# DVT-Discrete.net
KiCad netlist of a schematic drawn in Altium Designer
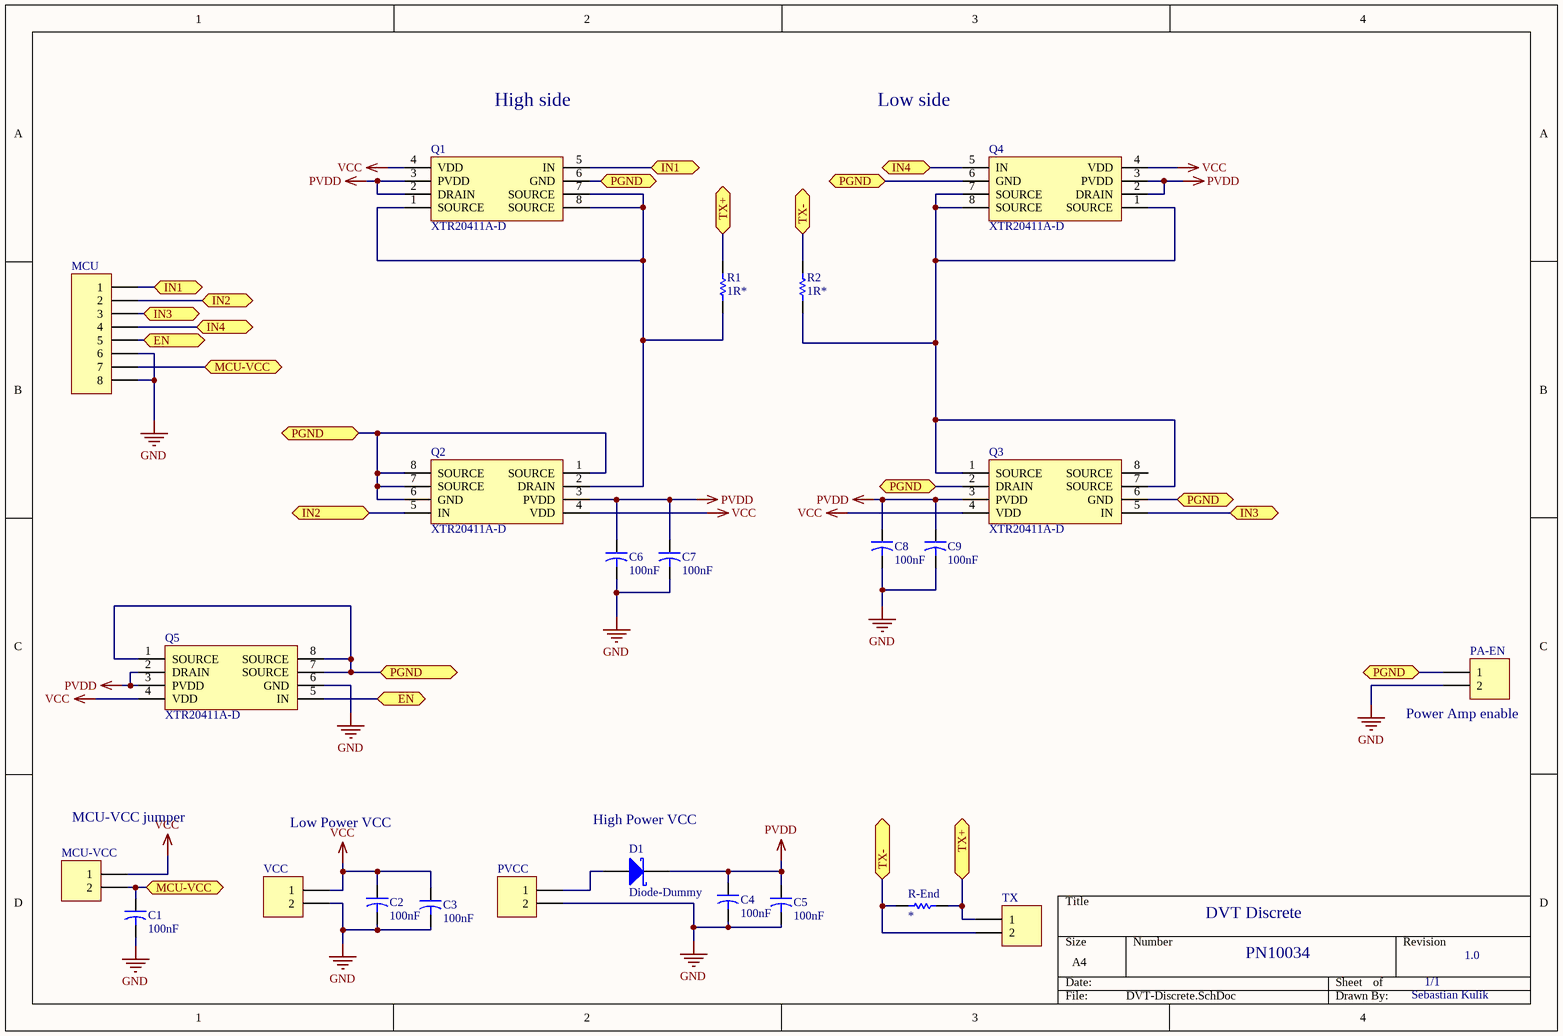
[diagram p0: DVT-Discrete.SchDoc]

(export (version "E")
  (design (tool "Eeschema 10.0.6"))
  (components
    (comp (ref "C1")
      (value "100nF")
      (footprint "Dummy-10mm")
      (description "Capacitor-Dummy-THT")
      (fields (field (name "PUBLISHER") "Sebastian Kulik"))
      (libsource (lib "Capacitors") (part "Capacitor-Dummy-THT"))
    )
    (comp (ref "C2")
      (value "100nF")
      (footprint "Dummy-10mm")
      (description "Capacitor-Dummy-THT")
      (fields (field (name "PUBLISHER") "Sebastian Kulik"))
      (libsource (lib "Capacitors") (part "Capacitor-Dummy-THT"))
    )
    (comp (ref "C3")
      (value "100nF")
      (footprint "Dummy-10mm")
      (description "Capacitor-Dummy-THT")
      (fields (field (name "PUBLISHER") "Sebastian Kulik"))
      (libsource (lib "Capacitors") (part "Capacitor-Dummy-THT"))
    )
    (comp (ref "C4")
      (value "100nF")
      (footprint "Dummy-10mm")
      (description "Capacitor-Dummy-THT")
      (fields (field (name "PUBLISHER") "Sebastian Kulik"))
      (libsource (lib "Capacitors") (part "Capacitor-Dummy-THT"))
    )
    (comp (ref "C5")
      (value "100nF")
      (footprint "Dummy-10mm")
      (description "Capacitor-Dummy-THT")
      (fields (field (name "PUBLISHER") "Sebastian Kulik"))
      (libsource (lib "Capacitors") (part "Capacitor-Dummy-THT"))
    )
    (comp (ref "C6")
      (value "100nF")
      (footprint "Dummy-10mm")
      (description "Capacitor-Dummy-THT")
      (fields (field (name "PUBLISHER") "Sebastian Kulik"))
      (libsource (lib "Capacitors") (part "Capacitor-Dummy-THT"))
    )
    (comp (ref "C7")
      (value "100nF")
      (footprint "Dummy-10mm")
      (description "Capacitor-Dummy-THT")
      (fields (field (name "PUBLISHER") "Sebastian Kulik"))
      (libsource (lib "Capacitors") (part "Capacitor-Dummy-THT"))
    )
    (comp (ref "C8")
      (value "100nF")
      (footprint "Dummy-10mm")
      (description "Capacitor-Dummy-THT")
      (fields (field (name "PUBLISHER") "Sebastian Kulik"))
      (libsource (lib "Capacitors") (part "Capacitor-Dummy-THT"))
    )
    (comp (ref "C9")
      (value "100nF")
      (footprint "Dummy-10mm")
      (description "Capacitor-Dummy-THT")
      (fields (field (name "PUBLISHER") "Sebastian Kulik"))
      (libsource (lib "Capacitors") (part "Capacitor-Dummy-THT"))
    )
    (comp (ref "D1")
      (value "Diode-Dummy")
      (footprint "DO-15-Dummy")
      (fields (field (name "PUBLISHER") "Sebastian Kulik"))
      (libsource (lib "Discrete") (part "Diode-Dummy"))
    )
    (comp (ref "MCU")
      (value "Plug_08_2.54")
      (footprint "HDR1X8_2.54")
      (description "Plug, 08-Pin")
      (fields (field (name "MANUFACTURER") "WE") (field (name "PUBLISHER") "Sebastian Kulik"))
      (libsource (lib "Connectors") (part "Plug_08_2.54"))
    )
    (comp (ref "MCU-VCC")
      (value "Plug_2_90_2.54")
      (footprint "HDR1X2")
      (description "Plug, 2-Pin")
      (fields (field (name "MANUFACTURER") "WE") (field (name "PUBLISHER") "Sebastian Kulik"))
      (libsource (lib "Connectors") (part "Plug_2_90_2.54"))
    )
    (comp (ref "PA-EN")
      (value "Plug_2_90_2.54")
      (footprint "HDR1X2")
      (description "Plug, 2-Pin")
      (fields (field (name "MANUFACTURER") "WE") (field (name "PUBLISHER") "Sebastian Kulik"))
      (libsource (lib "") (part "Plug_2_90_2.54_1"))
    )
    (comp (ref "PVCC")
      (value "PHOENIX_1715721")
      (footprint "Phoenix-2-5_08")
      (description "Phoenix, 2 pol, 5.08mm, 22A, 715721")
      (fields (field (name "MANUFACTURER") "Phoenix") (field (name "PUBLISHER") "Sebastian Kulik"))
      (libsource (lib "") (part "2Pol_1715721_1"))
    )
    (comp (ref "Q1")
      (value "XTR20411A-D")
      (footprint "DIP-8-Ceramic-HT")
      (description "Gate driver")
      (fields (field (name "MANUFACTURER") "X-Rel") (field (name "PUBLISHER") "Sebastian Kulik"))
      (libsource (lib "ICs") (part "XTR20411A-D"))
    )
    (comp (ref "Q2")
      (value "XTR20411A-D")
      (footprint "DIP-8-Ceramic-HT")
      (description "Gate driver")
      (fields (field (name "MANUFACTURER") "X-Rel") (field (name "PUBLISHER") "Sebastian Kulik"))
      (libsource (lib "") (part "XTR20411A-D_2"))
    )
    (comp (ref "Q3")
      (value "XTR20411A-D")
      (footprint "DIP-8-Ceramic-HT")
      (description "Gate driver")
      (fields (field (name "MANUFACTURER") "X-Rel") (field (name "PUBLISHER") "Sebastian Kulik"))
      (libsource (lib "") (part "XTR20411A-D_1"))
    )
    (comp (ref "Q4")
      (value "XTR20411A-D")
      (footprint "DIP-8-Ceramic-HT")
      (description "Gate driver")
      (fields (field (name "MANUFACTURER") "X-Rel") (field (name "PUBLISHER") "Sebastian Kulik"))
      (libsource (lib "") (part "XTR20411A-D_3"))
    )
    (comp (ref "Q5")
      (value "XTR20411A-D")
      (footprint "DIP-8-Ceramic-HT")
      (description "Gate driver")
      (fields (field (name "MANUFACTURER") "X-Rel") (field (name "PUBLISHER") "Sebastian Kulik"))
      (libsource (lib "") (part "XTR20411A-D_1"))
    )
    (comp (ref "R-End")
      (value "Resistor-Dummy-THT")
      (footprint "Dummy-10mm")
      (fields (field (name "ALTIUM_VALUE") "*") (field (name "PUBLISHER") "Sebastian Kulik"))
      (libsource (lib "Resistors") (part "Resistor-Dummy-THT"))
    )
    (comp (ref "R1")
      (value "1R*")
      (footprint "Dummy-10mm")
      (description "Resistor-Dummy-THT")
      (fields (field (name "PUBLISHER") "Sebastian Kulik"))
      (libsource (lib "Resistors") (part "Resistor-Dummy-THT"))
    )
    (comp (ref "R2")
      (value "1R*")
      (footprint "Dummy-10mm")
      (description "Resistor-Dummy-THT")
      (fields (field (name "PUBLISHER") "Sebastian Kulik"))
      (libsource (lib "Resistors") (part "Resistor-Dummy-THT"))
    )
    (comp (ref "TX")
      (value "PHOENIX_1715721")
      (footprint "Phoenix-2-5_08")
      (description "Phoenix, 2 pol, 5.08mm, 22A, 715721")
      (fields (field (name "MANUFACTURER") "Phoenix") (field (name "PUBLISHER") "Sebastian Kulik"))
      (libsource (lib "Connectors") (part "2Pol_1715721"))
    )
    (comp (ref "VCC")
      (value "PHOENIX_1715721")
      (footprint "Phoenix-2-5_08")
      (description "Phoenix, 2 pol, 5.08mm, 22A, 715721")
      (fields (field (name "MANUFACTURER") "Phoenix") (field (name "PUBLISHER") "Sebastian Kulik"))
      (libsource (lib "") (part "2Pol_1715721_1"))
    )
  )
  (nets
    (net (code "1") (name "/EN") (class "Default")
      (node (ref "MCU") (pin "5") (pinfunction "5_5") (pintype "passive"))
      (node (ref "Q5") (pin "5") (pinfunction "IN_5") (pintype "passive"))
    )
    (net (code "2") (name "/IN1") (class "Default")
      (node (ref "MCU") (pin "1") (pinfunction "1_1") (pintype "passive"))
      (node (ref "Q1") (pin "5") (pinfunction "IN_5") (pintype "passive"))
    )
    (net (code "3") (name "/IN2") (class "Default")
      (node (ref "MCU") (pin "2") (pinfunction "2_2") (pintype "passive"))
      (node (ref "Q2") (pin "5") (pinfunction "IN_5") (pintype "passive"))
    )
    (net (code "4") (name "/IN3") (class "Default")
      (node (ref "MCU") (pin "3") (pinfunction "3_3") (pintype "passive"))
      (node (ref "Q3") (pin "5") (pinfunction "IN_5") (pintype "passive"))
    )
    (net (code "5") (name "/IN4") (class "Default")
      (node (ref "MCU") (pin "4") (pinfunction "4_4") (pintype "passive"))
      (node (ref "Q4") (pin "5") (pinfunction "IN_5") (pintype "passive"))
    )
    (net (code "6") (name "/MCU-VCC") (class "Default")
      (node (ref "C1") (pin "1") (pinfunction "1_1") (pintype "passive"))
      (node (ref "MCU") (pin "7") (pinfunction "7_7") (pintype "passive"))
      (node (ref "MCU-VCC") (pin "2") (pinfunction "2_2") (pintype "passive"))
    )
    (net (code "7") (name "/PGND") (class "Default")
      (node (ref "PA-EN") (pin "1") (pinfunction "1_1") (pintype "passive"))
      (node (ref "Q1") (pin "6") (pinfunction "GND_6") (pintype "passive"))
      (node (ref "Q2") (pin "1") (pinfunction "SOURCE_1") (pintype "passive"))
      (node (ref "Q2") (pin "6") (pinfunction "GND_6") (pintype "passive"))
      (node (ref "Q2") (pin "7") (pinfunction "SOURCE_7") (pintype "passive"))
      (node (ref "Q2") (pin "8") (pinfunction "SOURCE_8") (pintype "passive"))
      (node (ref "Q3") (pin "2") (pinfunction "DRAIN_2") (pintype "passive"))
      (node (ref "Q3") (pin "6") (pinfunction "GND_6") (pintype "passive"))
      (node (ref "Q4") (pin "6") (pinfunction "GND_6") (pintype "passive"))
      (node (ref "Q5") (pin "1") (pinfunction "SOURCE_1") (pintype "passive"))
      (node (ref "Q5") (pin "7") (pinfunction "SOURCE_7") (pintype "passive"))
      (node (ref "Q5") (pin "8") (pinfunction "SOURCE_8") (pintype "passive"))
    )
    (net (code "8") (name "/TX+") (class "Default")
      (node (ref "R-End") (pin "2") (pinfunction "2_2") (pintype "passive"))
      (node (ref "R1") (pin "2") (pinfunction "2_2") (pintype "passive"))
      (node (ref "TX") (pin "1") (pinfunction "1_1") (pintype "passive"))
    )
    (net (code "9") (name "/TX-") (class "Default")
      (node (ref "R-End") (pin "1") (pinfunction "1_1") (pintype "passive"))
      (node (ref "R2") (pin "2") (pinfunction "2_2") (pintype "passive"))
      (node (ref "TX") (pin "2") (pinfunction "2_2") (pintype "passive"))
    )
    (net (code "10") (name "GND") (class "Default")
      (node (ref "C1") (pin "2") (pinfunction "2_2") (pintype "passive"))
      (node (ref "C2") (pin "2") (pinfunction "2_2") (pintype "passive"))
      (node (ref "C3") (pin "2") (pinfunction "2_2") (pintype "passive"))
      (node (ref "C4") (pin "2") (pinfunction "2_2") (pintype "passive"))
      (node (ref "C5") (pin "2") (pinfunction "2_2") (pintype "passive"))
      (node (ref "C6") (pin "2") (pinfunction "2_2") (pintype "passive"))
      (node (ref "C7") (pin "2") (pinfunction "2_2") (pintype "passive"))
      (node (ref "C8") (pin "2") (pinfunction "2_2") (pintype "passive"))
      (node (ref "C9") (pin "2") (pinfunction "2_2") (pintype "passive"))
      (node (ref "MCU") (pin "6") (pinfunction "6_6") (pintype "passive"))
      (node (ref "MCU") (pin "8") (pinfunction "8_8") (pintype "passive"))
      (node (ref "PA-EN") (pin "2") (pinfunction "2_2") (pintype "passive"))
      (node (ref "PVCC") (pin "2") (pinfunction "2_2") (pintype "passive"))
      (node (ref "Q5") (pin "6") (pinfunction "GND_6") (pintype "passive"))
      (node (ref "VCC") (pin "2") (pinfunction "2_2") (pintype "passive"))
    )
    (net (code "11") (name "Net-(D1-A)") (class "Default")
      (node (ref "D1") (pin "2") (pinfunction "A_2") (pintype "passive"))
      (node (ref "PVCC") (pin "1") (pinfunction "1_1") (pintype "passive"))
    )
    (net (code "12") (name "Net-(Q2-DRAIN)") (class "Default")
      (node (ref "Q1") (pin "1") (pinfunction "SOURCE_1") (pintype "passive"))
      (node (ref "Q1") (pin "7") (pinfunction "SOURCE_7") (pintype "passive"))
      (node (ref "Q1") (pin "8") (pinfunction "SOURCE_8") (pintype "passive"))
      (node (ref "Q2") (pin "2") (pinfunction "DRAIN_2") (pintype "passive"))
      (node (ref "R1") (pin "1") (pinfunction "1_1") (pintype "passive"))
    )
    (net (code "13") (name "Net-(Q3-SOURCE-Pad1)") (class "Default")
      (node (ref "Q3") (pin "1") (pinfunction "SOURCE_1") (pintype "passive"))
      (node (ref "Q3") (pin "7") (pinfunction "SOURCE_7") (pintype "passive"))
      (node (ref "Q4") (pin "1") (pinfunction "SOURCE_1") (pintype "passive"))
      (node (ref "Q4") (pin "7") (pinfunction "SOURCE_7") (pintype "passive"))
      (node (ref "Q4") (pin "8") (pinfunction "SOURCE_8") (pintype "passive"))
      (node (ref "R2") (pin "1") (pinfunction "1_1") (pintype "passive"))
    )
    (net (code "14") (name "PVDD") (class "Default")
      (node (ref "C4") (pin "1") (pinfunction "1_1") (pintype "passive"))
      (node (ref "C5") (pin "1") (pinfunction "1_1") (pintype "passive"))
      (node (ref "C6") (pin "1") (pinfunction "1_1") (pintype "passive"))
      (node (ref "C7") (pin "1") (pinfunction "1_1") (pintype "passive"))
      (node (ref "C8") (pin "1") (pinfunction "1_1") (pintype "passive"))
      (node (ref "C9") (pin "1") (pinfunction "1_1") (pintype "passive"))
      (node (ref "D1") (pin "1") (pinfunction "K_1") (pintype "passive"))
      (node (ref "Q1") (pin "2") (pinfunction "DRAIN_2") (pintype "passive"))
      (node (ref "Q1") (pin "3") (pinfunction "PVDD_3") (pintype "passive"))
      (node (ref "Q2") (pin "3") (pinfunction "PVDD_3") (pintype "passive"))
      (node (ref "Q3") (pin "3") (pinfunction "PVDD_3") (pintype "passive"))
      (node (ref "Q4") (pin "2") (pinfunction "DRAIN_2") (pintype "passive"))
      (node (ref "Q4") (pin "3") (pinfunction "PVDD_3") (pintype "passive"))
      (node (ref "Q5") (pin "2") (pinfunction "DRAIN_2") (pintype "passive"))
      (node (ref "Q5") (pin "3") (pinfunction "PVDD_3") (pintype "passive"))
    )
    (net (code "15") (name "VCC") (class "Default")
      (node (ref "C2") (pin "1") (pinfunction "1_1") (pintype "passive"))
      (node (ref "C3") (pin "1") (pinfunction "1_1") (pintype "passive"))
      (node (ref "MCU-VCC") (pin "1") (pinfunction "1_1") (pintype "passive"))
      (node (ref "Q1") (pin "4") (pinfunction "VDD_4") (pintype "passive"))
      (node (ref "Q2") (pin "4") (pinfunction "VDD_4") (pintype "passive"))
      (node (ref "Q3") (pin "4") (pinfunction "VDD_4") (pintype "passive"))
      (node (ref "Q4") (pin "4") (pinfunction "VDD_4") (pintype "passive"))
      (node (ref "Q5") (pin "4") (pinfunction "VDD_4") (pintype "passive"))
      (node (ref "VCC") (pin "1") (pinfunction "1_1") (pintype "passive"))
    )
    (net (code "16") (name "unconnected-(Q3-SOURCE-Pad8)") (class "Default")
      (node (ref "Q3") (pin "8") (pinfunction "SOURCE_8") (pintype "passive"))
    )
  )
)
